# M90E36A.net
KiCad netlist of a schematic drawn in EAGLE
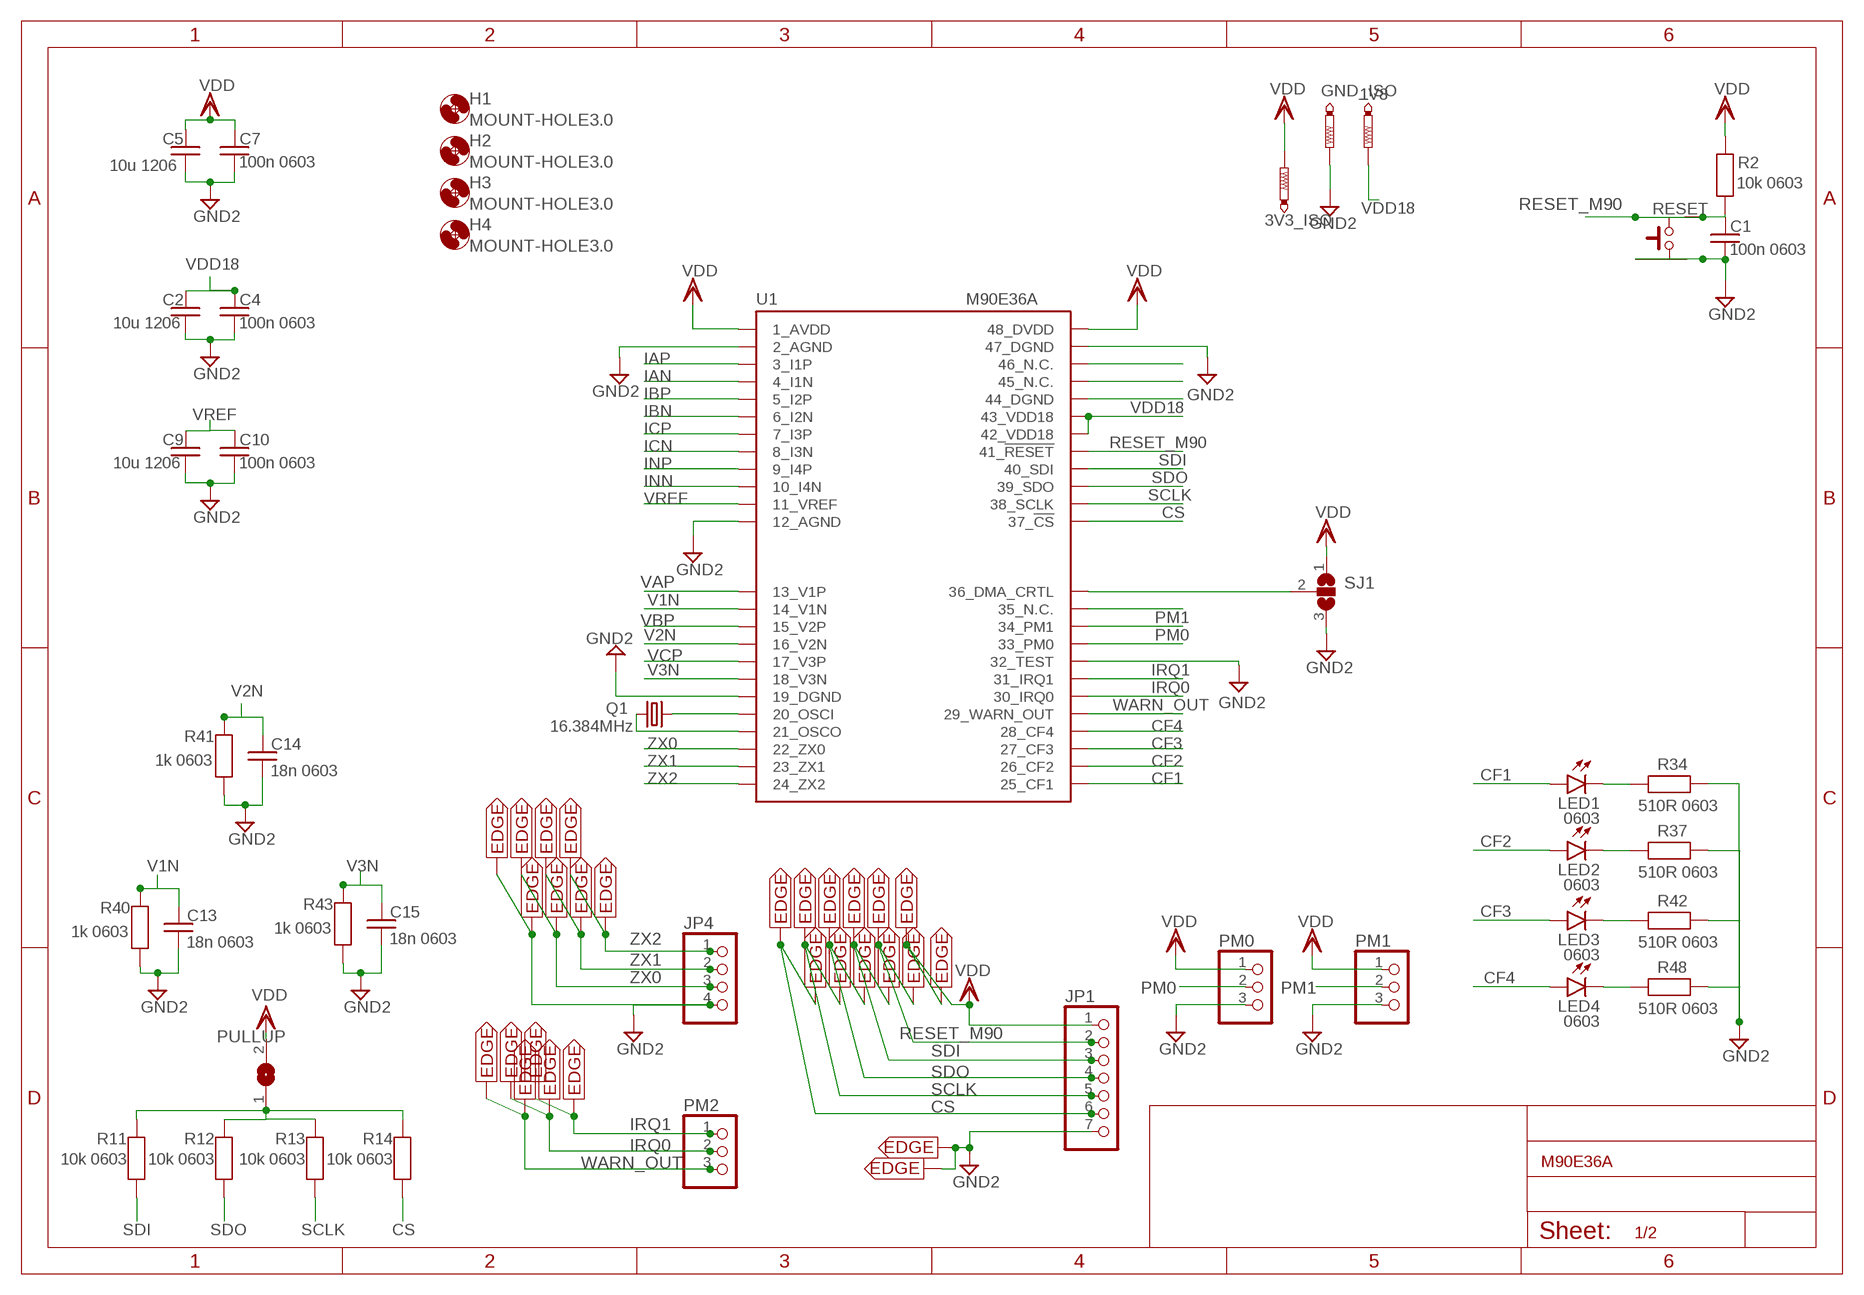
[diagram p0: schematic, sheet 1]
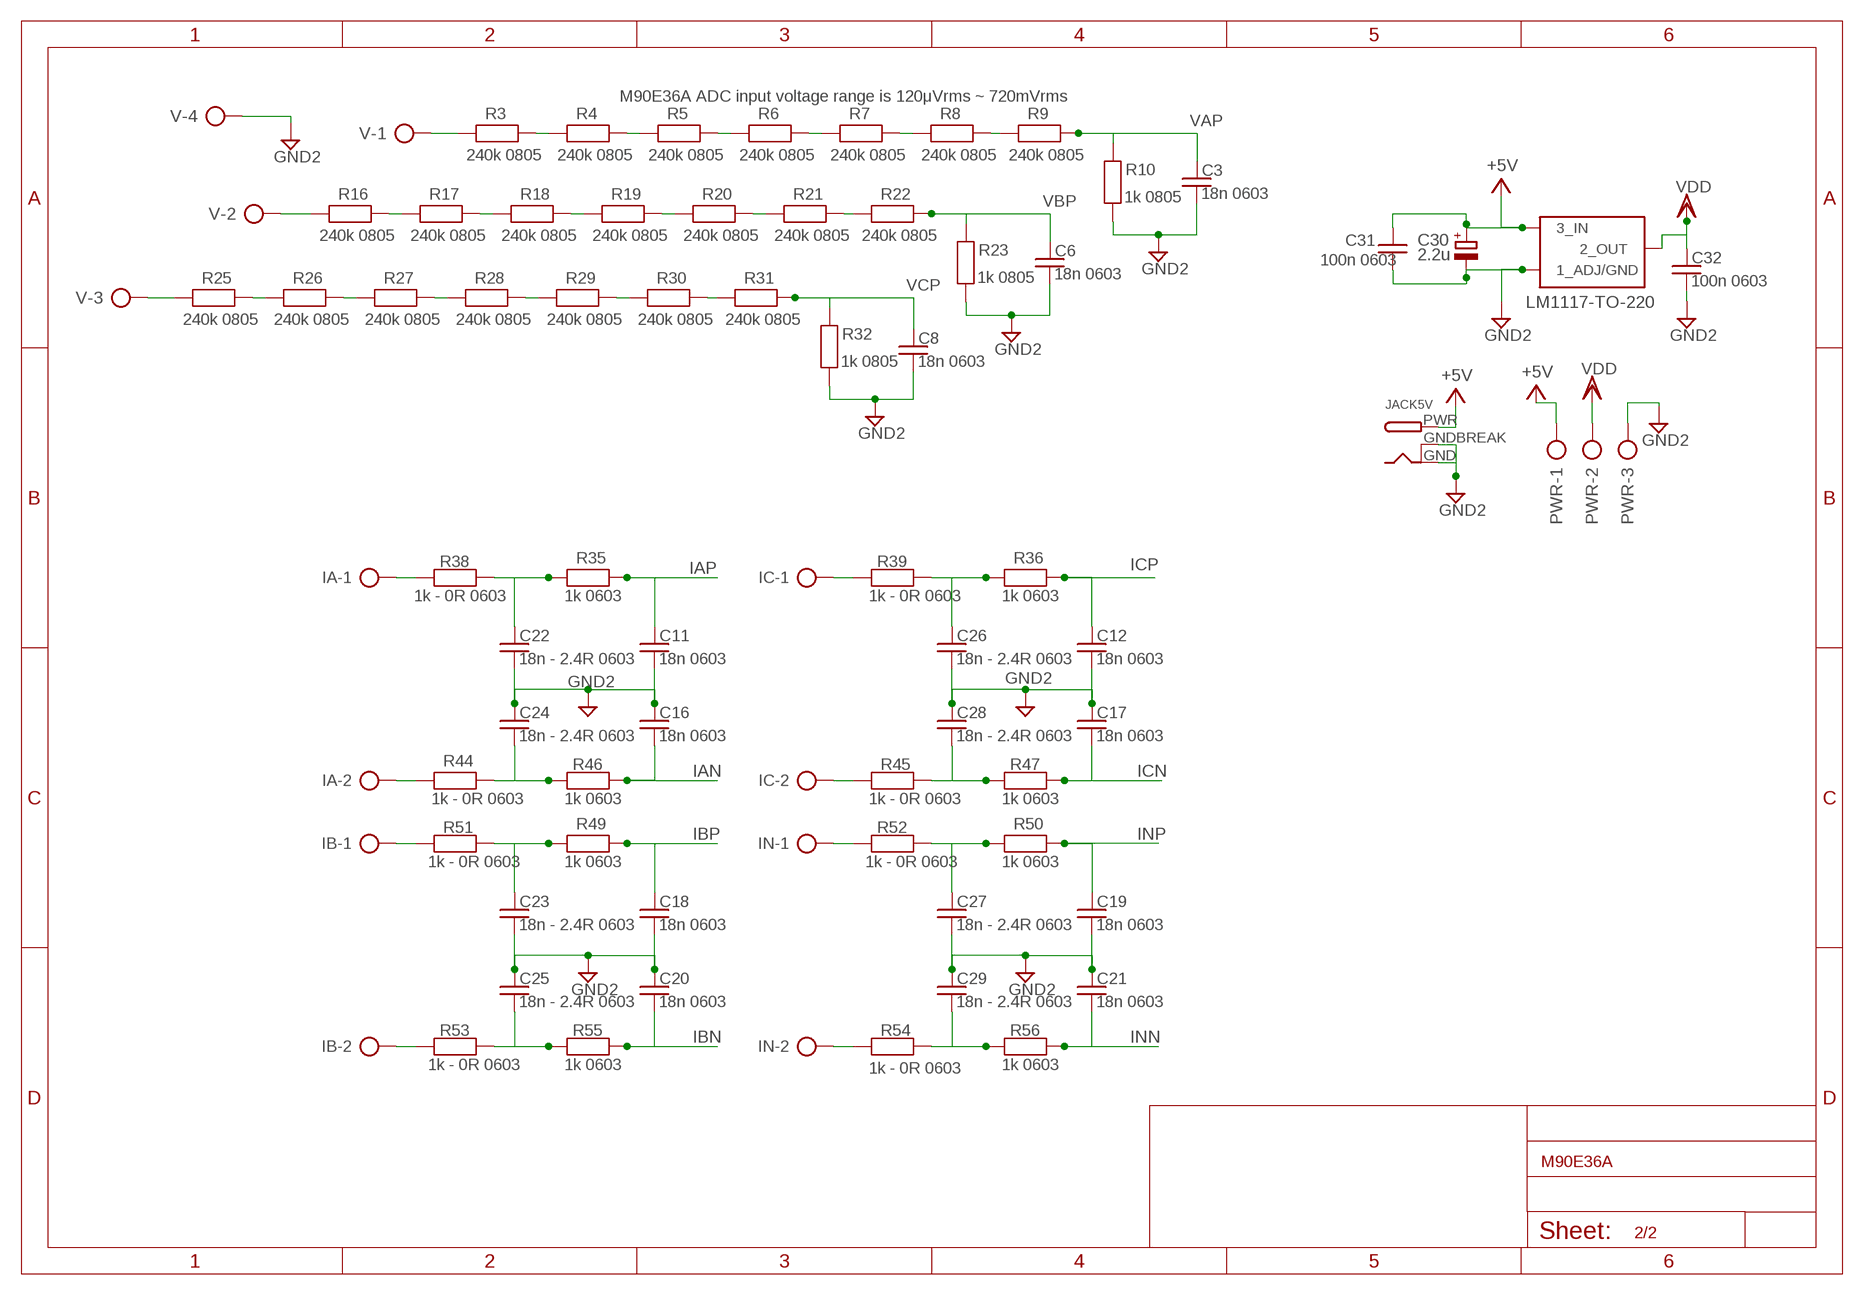
[diagram p1: schematic, sheet 2]

(export (version "E")
  (design (tool "Eeschema 10.0.6"))
  (components
    (comp (ref "C3")
      (value "18n 0603")
      (footprint "eagle-import:0603_IMPERIAL")
      (libsource (lib "eagle-import") (part "C0603"))
    )
    (comp (ref "C6")
      (value "18n 0603")
      (footprint "eagle-import:0603_IMPERIAL")
      (libsource (lib "eagle-import") (part "C0603"))
    )
    (comp (ref "C8")
      (value "18n 0603")
      (footprint "eagle-import:0603_IMPERIAL")
      (libsource (lib "eagle-import") (part "C0603"))
    )
    (comp (ref "C11")
      (value "18n 0603")
      (footprint "eagle-import:0603_IMPERIAL")
      (libsource (lib "eagle-import") (part "C0603"))
    )
    (comp (ref "C12")
      (value "18n 0603")
      (footprint "eagle-import:0603_IMPERIAL")
      (libsource (lib "eagle-import") (part "C0603"))
    )
    (comp (ref "C16")
      (value "18n 0603")
      (footprint "eagle-import:0603_IMPERIAL")
      (libsource (lib "eagle-import") (part "C0603"))
    )
    (comp (ref "C17")
      (value "18n 0603")
      (footprint "eagle-import:0603_IMPERIAL")
      (libsource (lib "eagle-import") (part "C0603"))
    )
    (comp (ref "C18")
      (value "18n 0603")
      (footprint "eagle-import:0603_IMPERIAL")
      (libsource (lib "eagle-import") (part "C0603"))
    )
    (comp (ref "C19")
      (value "18n 0603")
      (footprint "eagle-import:0603_IMPERIAL")
      (libsource (lib "eagle-import") (part "C0603"))
    )
    (comp (ref "C20")
      (value "18n 0603")
      (footprint "eagle-import:0603_IMPERIAL")
      (libsource (lib "eagle-import") (part "C0603"))
    )
    (comp (ref "C21")
      (value "18n 0603")
      (footprint "eagle-import:0603_IMPERIAL")
      (libsource (lib "eagle-import") (part "C0603"))
    )
    (comp (ref "C22")
      (value "18n - 2.4R 0603")
      (footprint "eagle-import:0603_IMPERIAL")
      (libsource (lib "eagle-import") (part "C0603"))
    )
    (comp (ref "C23")
      (value "18n - 2.4R 0603")
      (footprint "eagle-import:0603_IMPERIAL")
      (libsource (lib "eagle-import") (part "C0603"))
    )
    (comp (ref "C24")
      (value "18n - 2.4R 0603")
      (footprint "eagle-import:0603_IMPERIAL")
      (libsource (lib "eagle-import") (part "C0603"))
    )
    (comp (ref "C25")
      (value "18n - 2.4R 0603")
      (footprint "eagle-import:0603_IMPERIAL")
      (libsource (lib "eagle-import") (part "C0603"))
    )
    (comp (ref "C26")
      (value "18n - 2.4R 0603")
      (footprint "eagle-import:0603_IMPERIAL")
      (libsource (lib "eagle-import") (part "C0603"))
    )
    (comp (ref "C27")
      (value "18n - 2.4R 0603")
      (footprint "eagle-import:0603_IMPERIAL")
      (libsource (lib "eagle-import") (part "C0603"))
    )
    (comp (ref "C28")
      (value "18n - 2.4R 0603")
      (footprint "eagle-import:0603_IMPERIAL")
      (libsource (lib "eagle-import") (part "C0603"))
    )
    (comp (ref "C29")
      (value "18n - 2.4R 0603")
      (footprint "eagle-import:0603_IMPERIAL")
      (libsource (lib "eagle-import") (part "C0603"))
    )
    (comp (ref "C30")
      (value "2.2u")
      (footprint "eagle-import:E2,5-5")
      (libsource (lib "eagle-import") (part "CPOL-EUE2.5-5"))
    )
    (comp (ref "C31")
      (value "100n 0603")
      (footprint "eagle-import:0603_IMPERIAL")
      (libsource (lib "eagle-import") (part "C0603"))
    )
    (comp (ref "C32")
      (value "100n 0603")
      (footprint "eagle-import:0603_IMPERIAL")
      (libsource (lib "eagle-import") (part "C0603"))
    )
    (comp (ref "IA")
      (value "AK500/2")
      (footprint "eagle-import:AK500_2")
      (libsource (lib "eagle-import") (part "AK500/2"))
    )
    (comp (ref "IB")
      (value "AK500/2")
      (footprint "eagle-import:AK500_2")
      (libsource (lib "eagle-import") (part "AK500/2"))
    )
    (comp (ref "IC")
      (value "AK500/2")
      (footprint "eagle-import:AK500_2")
      (libsource (lib "eagle-import") (part "AK500/2"))
    )
    (comp (ref "IN")
      (value "AK500/2")
      (footprint "eagle-import:AK500_2")
      (libsource (lib "eagle-import") (part "AK500/2"))
    )
    (comp (ref "JACK5V")
      (value "DCBARRELPTH")
      (footprint "eagle-import:DCJACK_2MM_PTH")
      (libsource (lib "eagle-import") (part "DCBARRELPTH"))
    )
    (comp (ref "PWR")
      (value "AK500/3")
      (footprint "eagle-import:AK500_3")
      (libsource (lib "eagle-import") (part "AK500/3"))
    )
    (comp (ref "R3")
      (value "240k 0805")
      (footprint "eagle-import:0805_IMPERIAL")
      (libsource (lib "eagle-import") (part "R0805"))
    )
    (comp (ref "R4")
      (value "240k 0805")
      (footprint "eagle-import:0805_IMPERIAL")
      (libsource (lib "eagle-import") (part "R0805"))
    )
    (comp (ref "R5")
      (value "240k 0805")
      (footprint "eagle-import:0805_IMPERIAL")
      (libsource (lib "eagle-import") (part "R0805"))
    )
    (comp (ref "R6")
      (value "240k 0805")
      (footprint "eagle-import:0805_IMPERIAL")
      (libsource (lib "eagle-import") (part "R0805"))
    )
    (comp (ref "R7")
      (value "240k 0805")
      (footprint "eagle-import:0805_IMPERIAL")
      (libsource (lib "eagle-import") (part "R0805"))
    )
    (comp (ref "R8")
      (value "240k 0805")
      (footprint "eagle-import:0805_IMPERIAL")
      (libsource (lib "eagle-import") (part "R0805"))
    )
    (comp (ref "R9")
      (value "240k 0805")
      (footprint "eagle-import:0805_IMPERIAL")
      (libsource (lib "eagle-import") (part "R0805"))
    )
    (comp (ref "R10")
      (value "1k 0805")
      (footprint "eagle-import:0805_IMPERIAL")
      (libsource (lib "eagle-import") (part "R0805"))
    )
    (comp (ref "R16")
      (value "240k 0805")
      (footprint "eagle-import:0805_IMPERIAL")
      (libsource (lib "eagle-import") (part "R0805"))
    )
    (comp (ref "R17")
      (value "240k 0805")
      (footprint "eagle-import:0805_IMPERIAL")
      (libsource (lib "eagle-import") (part "R0805"))
    )
    (comp (ref "R18")
      (value "240k 0805")
      (footprint "eagle-import:0805_IMPERIAL")
      (libsource (lib "eagle-import") (part "R0805"))
    )
    (comp (ref "R19")
      (value "240k 0805")
      (footprint "eagle-import:0805_IMPERIAL")
      (libsource (lib "eagle-import") (part "R0805"))
    )
    (comp (ref "R20")
      (value "240k 0805")
      (footprint "eagle-import:0805_IMPERIAL")
      (libsource (lib "eagle-import") (part "R0805"))
    )
    (comp (ref "R21")
      (value "240k 0805")
      (footprint "eagle-import:0805_IMPERIAL")
      (libsource (lib "eagle-import") (part "R0805"))
    )
    (comp (ref "R22")
      (value "240k 0805")
      (footprint "eagle-import:0805_IMPERIAL")
      (libsource (lib "eagle-import") (part "R0805"))
    )
    (comp (ref "R23")
      (value "1k 0805")
      (footprint "eagle-import:0805_IMPERIAL")
      (libsource (lib "eagle-import") (part "R0805"))
    )
    (comp (ref "R25")
      (value "240k 0805")
      (footprint "eagle-import:0805_IMPERIAL")
      (libsource (lib "eagle-import") (part "R0805"))
    )
    (comp (ref "R26")
      (value "240k 0805")
      (footprint "eagle-import:0805_IMPERIAL")
      (libsource (lib "eagle-import") (part "R0805"))
    )
    (comp (ref "R27")
      (value "240k 0805")
      (footprint "eagle-import:0805_IMPERIAL")
      (libsource (lib "eagle-import") (part "R0805"))
    )
    (comp (ref "R28")
      (value "240k 0805")
      (footprint "eagle-import:0805_IMPERIAL")
      (libsource (lib "eagle-import") (part "R0805"))
    )
    (comp (ref "R29")
      (value "240k 0805")
      (footprint "eagle-import:0805_IMPERIAL")
      (libsource (lib "eagle-import") (part "R0805"))
    )
    (comp (ref "R30")
      (value "240k 0805")
      (footprint "eagle-import:0805_IMPERIAL")
      (libsource (lib "eagle-import") (part "R0805"))
    )
    (comp (ref "R31")
      (value "240k 0805")
      (footprint "eagle-import:0805_IMPERIAL")
      (libsource (lib "eagle-import") (part "R0805"))
    )
    (comp (ref "R32")
      (value "1k 0805")
      (footprint "eagle-import:0805_IMPERIAL")
      (libsource (lib "eagle-import") (part "R0805"))
    )
    (comp (ref "R35")
      (value "1k 0603")
      (footprint "eagle-import:0603_IMPERIAL")
      (libsource (lib "eagle-import") (part "R0603"))
    )
    (comp (ref "R36")
      (value "1k 0603")
      (footprint "eagle-import:0603_IMPERIAL")
      (libsource (lib "eagle-import") (part "R0603"))
    )
    (comp (ref "R38")
      (value "1k - 0R 0603")
      (footprint "eagle-import:0603_IMPERIAL")
      (libsource (lib "eagle-import") (part "R0603"))
    )
    (comp (ref "R39")
      (value "1k - 0R 0603")
      (footprint "eagle-import:0603_IMPERIAL")
      (libsource (lib "eagle-import") (part "R0603"))
    )
    (comp (ref "R44")
      (value "1k - 0R 0603")
      (footprint "eagle-import:0603_IMPERIAL")
      (libsource (lib "eagle-import") (part "R0603"))
    )
    (comp (ref "R45")
      (value "1k - 0R 0603")
      (footprint "eagle-import:0603_IMPERIAL")
      (libsource (lib "eagle-import") (part "R0603"))
    )
    (comp (ref "R46")
      (value "1k 0603")
      (footprint "eagle-import:0603_IMPERIAL")
      (libsource (lib "eagle-import") (part "R0603"))
    )
    (comp (ref "R47")
      (value "1k 0603")
      (footprint "eagle-import:0603_IMPERIAL")
      (libsource (lib "eagle-import") (part "R0603"))
    )
    (comp (ref "R49")
      (value "1k 0603")
      (footprint "eagle-import:0603_IMPERIAL")
      (libsource (lib "eagle-import") (part "R0603"))
    )
    (comp (ref "R50")
      (value "1k 0603")
      (footprint "eagle-import:0603_IMPERIAL")
      (libsource (lib "eagle-import") (part "R0603"))
    )
    (comp (ref "R51")
      (value "1k - 0R 0603")
      (footprint "eagle-import:0603_IMPERIAL")
      (libsource (lib "eagle-import") (part "R0603"))
    )
    (comp (ref "R52")
      (value "1k - 0R 0603")
      (footprint "eagle-import:0603_IMPERIAL")
      (libsource (lib "eagle-import") (part "R0603"))
    )
    (comp (ref "R53")
      (value "1k - 0R 0603")
      (footprint "eagle-import:0603_IMPERIAL")
      (libsource (lib "eagle-import") (part "R0603"))
    )
    (comp (ref "R54")
      (value "1k - 0R 0603")
      (footprint "eagle-import:0603_IMPERIAL")
      (libsource (lib "eagle-import") (part "R0603"))
    )
    (comp (ref "R55")
      (value "1k 0603")
      (footprint "eagle-import:0603_IMPERIAL")
      (libsource (lib "eagle-import") (part "R0603"))
    )
    (comp (ref "R56")
      (value "1k 0603")
      (footprint "eagle-import:0603_IMPERIAL")
      (libsource (lib "eagle-import") (part "R0603"))
    )
    (comp (ref "U3")
      (value "LM1117-TO-220")
      (footprint "eagle-import:TO-220")
      (libsource (lib "eagle-import") (part "LM1117-TO-220"))
    )
    (comp (ref "V")
      (value "AK500/4")
      (footprint "eagle-import:AK500_4")
      (libsource (lib "eagle-import") (part "AK500/4"))
    )
    (comp (ref "1V8")
      (value "PTR1TP19R")
      (footprint "eagle-import:TP19R")
      (libsource (lib "eagle-import") (part "PTR1TP19R"))
    )
    (comp (ref "3V3_ISO")
      (value "PTR1TP19R")
      (footprint "eagle-import:TP19R")
      (libsource (lib "eagle-import") (part "PTR1TP19R"))
    )
    (comp (ref "C1")
      (value "100n 0603")
      (footprint "eagle-import:0603_IMPERIAL")
      (libsource (lib "eagle-import") (part "C0603"))
    )
    (comp (ref "C2")
      (value "10u 1206")
      (footprint "eagle-import:1206_IMPERIAL")
      (libsource (lib "eagle-import") (part "C1206"))
    )
    (comp (ref "C4")
      (value "100n 0603")
      (footprint "eagle-import:0603_IMPERIAL")
      (libsource (lib "eagle-import") (part "C0603"))
    )
    (comp (ref "C5")
      (value "10u 1206")
      (footprint "eagle-import:1206_IMPERIAL")
      (libsource (lib "eagle-import") (part "C1206"))
    )
    (comp (ref "C7")
      (value "100n 0603")
      (footprint "eagle-import:0603_IMPERIAL")
      (libsource (lib "eagle-import") (part "C0603"))
    )
    (comp (ref "C9")
      (value "10u 1206")
      (footprint "eagle-import:1206_IMPERIAL")
      (libsource (lib "eagle-import") (part "C1206"))
    )
    (comp (ref "C10")
      (value "100n 0603")
      (footprint "eagle-import:0603_IMPERIAL")
      (libsource (lib "eagle-import") (part "C0603"))
    )
    (comp (ref "C13")
      (value "18n 0603")
      (footprint "eagle-import:0603_IMPERIAL")
      (libsource (lib "eagle-import") (part "C0603"))
    )
    (comp (ref "C14")
      (value "18n 0603")
      (footprint "eagle-import:0603_IMPERIAL")
      (libsource (lib "eagle-import") (part "C0603"))
    )
    (comp (ref "C15")
      (value "18n 0603")
      (footprint "eagle-import:0603_IMPERIAL")
      (libsource (lib "eagle-import") (part "C0603"))
    )
    (comp (ref "GND_ISO")
      (value "PTR1TP19R")
      (footprint "eagle-import:TP19R")
      (libsource (lib "eagle-import") (part "PTR1TP19R"))
    )
    (comp (ref "H1")
      (value "MOUNT-HOLE3.0")
      (footprint "eagle-import:3,0")
      (libsource (lib "eagle-import") (part "MOUNT-HOLE3.0"))
    )
    (comp (ref "H2")
      (value "MOUNT-HOLE3.0")
      (footprint "eagle-import:3,0")
      (libsource (lib "eagle-import") (part "MOUNT-HOLE3.0"))
    )
    (comp (ref "H3")
      (value "MOUNT-HOLE3.0")
      (footprint "eagle-import:3,0")
      (libsource (lib "eagle-import") (part "MOUNT-HOLE3.0"))
    )
    (comp (ref "H4")
      (value "MOUNT-HOLE3.0")
      (footprint "eagle-import:3,0")
      (libsource (lib "eagle-import") (part "MOUNT-HOLE3.0"))
    )
    (comp (ref "JP1")
      (value "PINHD-1X7")
      (footprint "eagle-import:1X07")
      (libsource (lib "eagle-import") (part "PINHD-1X7"))
    )
    (comp (ref "JP4")
      (value "PINHD-1X4")
      (footprint "eagle-import:1X04")
      (libsource (lib "eagle-import") (part "PINHD-1X4"))
    )
    (comp (ref "LED1")
      (value "0603")
      (footprint "eagle-import:CHIPLED_0805")
      (libsource (lib "eagle-import") (part "LEDCHIPLED_0805"))
    )
    (comp (ref "LED2")
      (value "0603")
      (footprint "eagle-import:CHIPLED_0805")
      (libsource (lib "eagle-import") (part "LEDCHIPLED_0805"))
    )
    (comp (ref "LED3")
      (value "0603")
      (footprint "eagle-import:CHIPLED_0805")
      (libsource (lib "eagle-import") (part "LEDCHIPLED_0805"))
    )
    (comp (ref "LED4")
      (value "0603")
      (footprint "eagle-import:CHIPLED_0805")
      (libsource (lib "eagle-import") (part "LEDCHIPLED_0805"))
    )
    (comp (ref "PM0")
      (value "PINHD-1X3")
      (footprint "eagle-import:1X03")
      (libsource (lib "eagle-import") (part "PINHD-1X3"))
    )
    (comp (ref "PM1")
      (value "PINHD-1X3")
      (footprint "eagle-import:1X03")
      (libsource (lib "eagle-import") (part "PINHD-1X3"))
    )
    (comp (ref "PM2")
      (value "PINHD-1X3")
      (footprint "eagle-import:1X03")
      (libsource (lib "eagle-import") (part "PINHD-1X3"))
    )
    (comp (ref "PULLUP")
      (value "SJ")
      (footprint "eagle-import:SJ")
      (libsource (lib "eagle-import") (part "SJ"))
    )
    (comp (ref "Q1")
      (value "16.384MHz")
      (footprint "eagle-import:HC49UP")
      (libsource (lib "eagle-import") (part "CRYSTALHC49UP"))
    )
    (comp (ref "R2")
      (value "10k 0603")
      (footprint "eagle-import:0603_IMPERIAL")
      (libsource (lib "eagle-import") (part "R0603"))
    )
    (comp (ref "R11")
      (value "10k 0603")
      (footprint "eagle-import:0603_IMPERIAL")
      (libsource (lib "eagle-import") (part "R0603"))
    )
    (comp (ref "R12")
      (value "10k 0603")
      (footprint "eagle-import:0603_IMPERIAL")
      (libsource (lib "eagle-import") (part "R0603"))
    )
    (comp (ref "R13")
      (value "10k 0603")
      (footprint "eagle-import:0603_IMPERIAL")
      (libsource (lib "eagle-import") (part "R0603"))
    )
    (comp (ref "R14")
      (value "10k 0603")
      (footprint "eagle-import:0603_IMPERIAL")
      (libsource (lib "eagle-import") (part "R0603"))
    )
    (comp (ref "R34")
      (value "510R 0603")
      (footprint "eagle-import:0603_IMPERIAL")
      (libsource (lib "eagle-import") (part "R0603"))
    )
    (comp (ref "R37")
      (value "510R 0603")
      (footprint "eagle-import:0603_IMPERIAL")
      (libsource (lib "eagle-import") (part "R0603"))
    )
    (comp (ref "R40")
      (value "1k 0603")
      (footprint "eagle-import:0603_IMPERIAL")
      (libsource (lib "eagle-import") (part "R0603"))
    )
    (comp (ref "R41")
      (value "1k 0603")
      (footprint "eagle-import:0603_IMPERIAL")
      (libsource (lib "eagle-import") (part "R0603"))
    )
    (comp (ref "R42")
      (value "510R 0603")
      (footprint "eagle-import:0603_IMPERIAL")
      (libsource (lib "eagle-import") (part "R0603"))
    )
    (comp (ref "R43")
      (value "1k 0603")
      (footprint "eagle-import:0603_IMPERIAL")
      (libsource (lib "eagle-import") (part "R0603"))
    )
    (comp (ref "R48")
      (value "510R 0603")
      (footprint "eagle-import:0603_IMPERIAL")
      (libsource (lib "eagle-import") (part "R0603"))
    )
    (comp (ref "RESET")
      (value "TACTILE_SWITCHPTH")
      (footprint "eagle-import:TACTILE_SWITCH_PTH")
      (fields (field (name "PARTNUMBER") "A06"))
      (libsource (lib "eagle-import") (part "TACTILE_SWITCHPTH"))
    )
    (comp (ref "SJ1")
      (value "SJ2W")
      (footprint "eagle-import:SJ_2")
      (libsource (lib "eagle-import") (part "SJ2W"))
    )
    (comp (ref "U$1")
      (value "EDGE")
      (footprint "eagle-import:EDGE")
      (libsource (lib "eagle-import") (part "EDGE"))
    )
    (comp (ref "U$2")
      (value "EDGE")
      (footprint "eagle-import:EDGE")
      (libsource (lib "eagle-import") (part "EDGE"))
    )
    (comp (ref "U$3")
      (value "EDGE")
      (footprint "eagle-import:EDGE")
      (libsource (lib "eagle-import") (part "EDGE"))
    )
    (comp (ref "U$4")
      (value "EDGE")
      (footprint "eagle-import:EDGE")
      (libsource (lib "eagle-import") (part "EDGE"))
    )
    (comp (ref "U$5")
      (value "EDGE")
      (footprint "eagle-import:EDGE")
      (libsource (lib "eagle-import") (part "EDGE"))
    )
    (comp (ref "U$6")
      (value "EDGE")
      (footprint "eagle-import:EDGE")
      (libsource (lib "eagle-import") (part "EDGE"))
    )
    (comp (ref "U$7")
      (value "EDGE")
      (footprint "eagle-import:EDGE")
      (libsource (lib "eagle-import") (part "EDGE"))
    )
    (comp (ref "U$8")
      (value "EDGE")
      (footprint "eagle-import:EDGE")
      (libsource (lib "eagle-import") (part "EDGE"))
    )
    (comp (ref "U$9")
      (value "EDGE")
      (footprint "eagle-import:EDGE")
      (libsource (lib "eagle-import") (part "EDGE"))
    )
    (comp (ref "U$10")
      (value "EDGE")
      (footprint "eagle-import:EDGE")
      (libsource (lib "eagle-import") (part "EDGE"))
    )
    (comp (ref "U$11")
      (value "EDGE")
      (footprint "eagle-import:EDGE")
      (libsource (lib "eagle-import") (part "EDGE"))
    )
    (comp (ref "U$12")
      (value "EDGE")
      (footprint "eagle-import:EDGE")
      (libsource (lib "eagle-import") (part "EDGE"))
    )
    (comp (ref "U$13")
      (value "EDGE")
      (footprint "eagle-import:EDGE")
      (libsource (lib "eagle-import") (part "EDGE"))
    )
    (comp (ref "U$14")
      (value "EDGE")
      (footprint "eagle-import:EDGE")
      (libsource (lib "eagle-import") (part "EDGE"))
    )
    (comp (ref "U$15")
      (value "EDGE")
      (footprint "eagle-import:EDGE")
      (libsource (lib "eagle-import") (part "EDGE"))
    )
    (comp (ref "U$16")
      (value "EDGE")
      (footprint "eagle-import:EDGE")
      (libsource (lib "eagle-import") (part "EDGE"))
    )
    (comp (ref "U$17")
      (value "EDGE")
      (footprint "eagle-import:EDGE")
      (libsource (lib "eagle-import") (part "EDGE"))
    )
    (comp (ref "U$18")
      (value "EDGE")
      (footprint "eagle-import:EDGE")
      (libsource (lib "eagle-import") (part "EDGE"))
    )
    (comp (ref "U$19")
      (value "EDGE")
      (footprint "eagle-import:EDGE")
      (libsource (lib "eagle-import") (part "EDGE"))
    )
    (comp (ref "U$20")
      (value "EDGE")
      (footprint "eagle-import:EDGE")
      (libsource (lib "eagle-import") (part "EDGE"))
    )
    (comp (ref "U$21")
      (value "EDGE")
      (footprint "eagle-import:EDGE")
      (libsource (lib "eagle-import") (part "EDGE"))
    )
    (comp (ref "U$22")
      (value "EDGE")
      (footprint "eagle-import:EDGE")
      (libsource (lib "eagle-import") (part "EDGE"))
    )
    (comp (ref "U$23")
      (value "EDGE")
      (footprint "eagle-import:EDGE")
      (libsource (lib "eagle-import") (part "EDGE"))
    )
    (comp (ref "U$24")
      (value "EDGE")
      (footprint "eagle-import:EDGE")
      (libsource (lib "eagle-import") (part "EDGE"))
    )
    (comp (ref "U$25")
      (value "EDGE")
      (footprint "eagle-import:EDGE")
      (libsource (lib "eagle-import") (part "EDGE"))
    )
    (comp (ref "U$26")
      (value "EDGE")
      (footprint "eagle-import:EDGE")
      (libsource (lib "eagle-import") (part "EDGE"))
    )
    (comp (ref "U$27")
      (value "EDGE")
      (footprint "eagle-import:EDGE")
      (libsource (lib "eagle-import") (part "EDGE"))
    )
    (comp (ref "U$28")
      (value "EDGE")
      (footprint "eagle-import:EDGE")
      (libsource (lib "eagle-import") (part "EDGE"))
    )
    (comp (ref "U1")
      (value "M90E36A")
      (footprint "eagle-import:TQFP-48")
      (fields (field (name "PARTNUMBER") "ATM90E36A-AU-Y"))
      (libsource (lib "eagle-import") (part "M90E36A"))
    )
  )
  (nets
    (net (code "1") (name "+5V") (class "Default")
      (node (ref "C30") (pin "+") (pinfunction "+_+") (pintype "passive"))
      (node (ref "C31") (pin "P$2") (pinfunction "P$2_P$2") (pintype "bidirectional"))
      (node (ref "JACK5V") (pin "PWR") (pinfunction "PWR_PWR") (pintype "power_in"))
      (node (ref "PWR") (pin "1") (pinfunction "KL_1") (pintype "passive"))
      (node (ref "U3") (pin "3") (pinfunction "3_IN_3") (pintype "input"))
    )
    (net (code "2") (name "CF1") (class "Default")
      (node (ref "LED1") (pin "A") (pinfunction "A_A") (pintype "passive"))
      (node (ref "U1") (pin "P$25") (pinfunction "25_CF1_P$25") (pintype "bidirectional"))
    )
    (net (code "3") (name "CF2") (class "Default")
      (node (ref "LED2") (pin "A") (pinfunction "A_A") (pintype "passive"))
      (node (ref "U1") (pin "P$26") (pinfunction "26_CF2_P$26") (pintype "bidirectional"))
    )
    (net (code "4") (name "CF3") (class "Default")
      (node (ref "LED3") (pin "A") (pinfunction "A_A") (pintype "passive"))
      (node (ref "U1") (pin "P$27") (pinfunction "27_CF3_P$27") (pintype "bidirectional"))
    )
    (net (code "5") (name "CF4") (class "Default")
      (node (ref "LED4") (pin "A") (pinfunction "A_A") (pintype "passive"))
      (node (ref "U1") (pin "P$28") (pinfunction "28_CF4_P$28") (pintype "bidirectional"))
    )
    (net (code "6") (name "CS") (class "Default")
      (node (ref "JP1") (pin "6") (pinfunction "6_6") (pintype "passive"))
      (node (ref "R14") (pin "P$1") (pinfunction "P$1_P$1") (pintype "bidirectional"))
      (node (ref "U$25") (pin "P$1") (pinfunction "P$1_P$1") (pintype "bidirectional"))
      (node (ref "U$4") (pin "P$1") (pinfunction "P$1_P$1") (pintype "bidirectional"))
      (node (ref "U1") (pin "P$37") (pinfunction "37_~{CS}_P$37") (pintype "bidirectional"))
    )
    (net (code "7") (name "GND2") (class "Default")
      (node (ref "C1") (pin "P$1") (pinfunction "P$1_P$1") (pintype "bidirectional"))
      (node (ref "C10") (pin "P$1") (pinfunction "P$1_P$1") (pintype "bidirectional"))
      (node (ref "C11") (pin "P$1") (pinfunction "P$1_P$1") (pintype "bidirectional"))
      (node (ref "C12") (pin "P$1") (pinfunction "P$1_P$1") (pintype "bidirectional"))
      (node (ref "C13") (pin "P$1") (pinfunction "P$1_P$1") (pintype "bidirectional"))
      (node (ref "C14") (pin "P$1") (pinfunction "P$1_P$1") (pintype "bidirectional"))
      (node (ref "C15") (pin "P$1") (pinfunction "P$1_P$1") (pintype "bidirectional"))
      (node (ref "C16") (pin "P$2") (pinfunction "P$2_P$2") (pintype "bidirectional"))
      (node (ref "C17") (pin "P$2") (pinfunction "P$2_P$2") (pintype "bidirectional"))
      (node (ref "C18") (pin "P$1") (pinfunction "P$1_P$1") (pintype "bidirectional"))
      (node (ref "C19") (pin "P$1") (pinfunction "P$1_P$1") (pintype "bidirectional"))
      (node (ref "C2") (pin "P$1") (pinfunction "P$1_P$1") (pintype "bidirectional"))
      (node (ref "C20") (pin "P$2") (pinfunction "P$2_P$2") (pintype "bidirectional"))
      (node (ref "C21") (pin "P$2") (pinfunction "P$2_P$2") (pintype "bidirectional"))
      (node (ref "C22") (pin "P$1") (pinfunction "P$1_P$1") (pintype "bidirectional"))
      (node (ref "C23") (pin "P$1") (pinfunction "P$1_P$1") (pintype "bidirectional"))
      (node (ref "C24") (pin "P$2") (pinfunction "P$2_P$2") (pintype "bidirectional"))
      (node (ref "C25") (pin "P$2") (pinfunction "P$2_P$2") (pintype "bidirectional"))
      (node (ref "C26") (pin "P$1") (pinfunction "P$1_P$1") (pintype "bidirectional"))
      (node (ref "C27") (pin "P$1") (pinfunction "P$1_P$1") (pintype "bidirectional"))
      (node (ref "C28") (pin "P$2") (pinfunction "P$2_P$2") (pintype "bidirectional"))
      (node (ref "C29") (pin "P$2") (pinfunction "P$2_P$2") (pintype "bidirectional"))
      (node (ref "C3") (pin "P$1") (pinfunction "P$1_P$1") (pintype "bidirectional"))
      (node (ref "C30") (pin "-") (pinfunction "-_-") (pintype "passive"))
      (node (ref "C31") (pin "P$1") (pinfunction "P$1_P$1") (pintype "bidirectional"))
      (node (ref "C32") (pin "P$1") (pinfunction "P$1_P$1") (pintype "bidirectional"))
      (node (ref "C4") (pin "P$1") (pinfunction "P$1_P$1") (pintype "bidirectional"))
      (node (ref "C5") (pin "P$1") (pinfunction "P$1_P$1") (pintype "bidirectional"))
      (node (ref "C6") (pin "P$1") (pinfunction "P$1_P$1") (pintype "bidirectional"))
      (node (ref "C7") (pin "P$1") (pinfunction "P$1_P$1") (pintype "bidirectional"))
      (node (ref "C8") (pin "P$1") (pinfunction "P$1_P$1") (pintype "bidirectional"))
      (node (ref "C9") (pin "P$1") (pinfunction "P$1_P$1") (pintype "bidirectional"))
      (node (ref "GND_ISO") (pin "TP") (pinfunction "TP_TP") (pintype "input"))
      (node (ref "JACK5V") (pin "GND") (pinfunction "GND_GND") (pintype "power_in"))
      (node (ref "JACK5V") (pin "GNDBREAK") (pinfunction "GNDBREAK_GNDBREAK") (pintype "power_in"))
      (node (ref "JP1") (pin "7") (pinfunction "7_7") (pintype "passive"))
      (node (ref "JP4") (pin "4") (pinfunction "4_4") (pintype "passive"))
      (node (ref "PM0") (pin "3") (pinfunction "3_3") (pintype "passive"))
      (node (ref "PM1") (pin "3") (pinfunction "3_3") (pintype "passive"))
      (node (ref "PWR") (pin "3") (pinfunction "KL_3") (pintype "passive"))
      (node (ref "R10") (pin "P$1") (pinfunction "P$1_P$1") (pintype "bidirectional"))
      (node (ref "R23") (pin "P$1") (pinfunction "P$1_P$1") (pintype "bidirectional"))
      (node (ref "R32") (pin "P$1") (pinfunction "P$1_P$1") (pintype "bidirectional"))
      (node (ref "R34") (pin "P$2") (pinfunction "P$2_P$2") (pintype "bidirectional"))
      (node (ref "R37") (pin "P$2") (pinfunction "P$2_P$2") (pintype "bidirectional"))
      (node (ref "R40") (pin "P$1") (pinfunction "P$1_P$1") (pintype "bidirectional"))
      (node (ref "R41") (pin "P$1") (pinfunction "P$1_P$1") (pintype "bidirectional"))
      (node (ref "R42") (pin "P$2") (pinfunction "P$2_P$2") (pintype "bidirectional"))
      (node (ref "R43") (pin "P$1") (pinfunction "P$1_P$1") (pintype "bidirectional"))
      (node (ref "R48") (pin "P$2") (pinfunction "P$2_P$2") (pintype "bidirectional"))
      (node (ref "RESET") (pin "P$1") (pinfunction "1_P$1") (pintype "bidirectional"))
      (node (ref "RESET") (pin "P$2") (pinfunction "2_P$2") (pintype "bidirectional"))
      (node (ref "SJ1") (pin "3") (pinfunction "3_3") (pintype "passive"))
      (node (ref "U$10") (pin "P$1") (pinfunction "P$1_P$1") (pintype "bidirectional"))
      (node (ref "U$18") (pin "P$1") (pinfunction "P$1_P$1") (pintype "bidirectional"))
      (node (ref "U$28") (pin "P$1") (pinfunction "P$1_P$1") (pintype "bidirectional"))
      (node (ref "U$6") (pin "P$1") (pinfunction "P$1_P$1") (pintype "bidirectional"))
      (node (ref "U1") (pin "P$12") (pinfunction "12_AGND_P$12") (pintype "bidirectional"))
      (node (ref "U1") (pin "P$19") (pinfunction "19_DGND_P$19") (pintype "bidirectional"))
      (node (ref "U1") (pin "P$2") (pinfunction "2_AGND_P$2") (pintype "bidirectional"))
      (node (ref "U1") (pin "P$32") (pinfunction "32_TEST_P$32") (pintype "bidirectional"))
      (node (ref "U1") (pin "P$47") (pinfunction "47_DGND_P$47") (pintype "bidirectional"))
      (node (ref "U3") (pin "1") (pinfunction "1_ADJ/GND_1") (pintype "input"))
      (node (ref "V") (pin "4") (pinfunction "KL_4") (pintype "passive"))
    )
    (net (code "8") (name "IAN") (class "Default")
      (node (ref "C16") (pin "P$1") (pinfunction "P$1_P$1") (pintype "bidirectional"))
      (node (ref "R46") (pin "P$2") (pinfunction "P$2_P$2") (pintype "bidirectional"))
      (node (ref "U1") (pin "P$4") (pinfunction "4_I1N_P$4") (pintype "bidirectional"))
    )
    (net (code "9") (name "IAP") (class "Default")
      (node (ref "C11") (pin "P$2") (pinfunction "P$2_P$2") (pintype "bidirectional"))
      (node (ref "R35") (pin "P$2") (pinfunction "P$2_P$2") (pintype "bidirectional"))
      (node (ref "U1") (pin "P$3") (pinfunction "3_I1P_P$3") (pintype "bidirectional"))
    )
    (net (code "10") (name "IBN") (class "Default")
      (node (ref "C20") (pin "P$1") (pinfunction "P$1_P$1") (pintype "bidirectional"))
      (node (ref "R55") (pin "P$2") (pinfunction "P$2_P$2") (pintype "bidirectional"))
      (node (ref "U1") (pin "P$6") (pinfunction "6_I2N_P$6") (pintype "bidirectional"))
    )
    (net (code "11") (name "IBP") (class "Default")
      (node (ref "C18") (pin "P$2") (pinfunction "P$2_P$2") (pintype "bidirectional"))
      (node (ref "R49") (pin "P$2") (pinfunction "P$2_P$2") (pintype "bidirectional"))
      (node (ref "U1") (pin "P$5") (pinfunction "5_I2P_P$5") (pintype "bidirectional"))
    )
    (net (code "12") (name "ICN") (class "Default")
      (node (ref "C17") (pin "P$1") (pinfunction "P$1_P$1") (pintype "bidirectional"))
      (node (ref "R47") (pin "P$2") (pinfunction "P$2_P$2") (pintype "bidirectional"))
      (node (ref "U1") (pin "P$8") (pinfunction "8_I3N_P$8") (pintype "bidirectional"))
    )
    (net (code "13") (name "ICP") (class "Default")
      (node (ref "C12") (pin "P$2") (pinfunction "P$2_P$2") (pintype "bidirectional"))
      (node (ref "R36") (pin "P$2") (pinfunction "P$2_P$2") (pintype "bidirectional"))
      (node (ref "U1") (pin "P$7") (pinfunction "7_I3P_P$7") (pintype "bidirectional"))
    )
    (net (code "14") (name "INN") (class "Default")
      (node (ref "C21") (pin "P$1") (pinfunction "P$1_P$1") (pintype "bidirectional"))
      (node (ref "R56") (pin "P$2") (pinfunction "P$2_P$2") (pintype "bidirectional"))
      (node (ref "U1") (pin "P$10") (pinfunction "10_I4N_P$10") (pintype "bidirectional"))
    )
    (net (code "15") (name "INP") (class "Default")
      (node (ref "C19") (pin "P$2") (pinfunction "P$2_P$2") (pintype "bidirectional"))
      (node (ref "R50") (pin "P$2") (pinfunction "P$2_P$2") (pintype "bidirectional"))
      (node (ref "U1") (pin "P$9") (pinfunction "9_I4P_P$9") (pintype "bidirectional"))
    )
    (net (code "16") (name "IRQ0") (class "Default")
      (node (ref "PM2") (pin "2") (pinfunction "2_2") (pintype "passive"))
      (node (ref "U$12") (pin "P$1") (pinfunction "P$1_P$1") (pintype "bidirectional"))
      (node (ref "U$20") (pin "P$1") (pinfunction "P$1_P$1") (pintype "bidirectional"))
      (node (ref "U1") (pin "P$30") (pinfunction "30_IRQ0_P$30") (pintype "bidirectional"))
    )
    (net (code "17") (name "IRQ1") (class "Default")
      (node (ref "PM2") (pin "1") (pinfunction "1_1") (pintype "passive"))
      (node (ref "U$11") (pin "P$1") (pinfunction "P$1_P$1") (pintype "bidirectional"))
      (node (ref "U$19") (pin "P$1") (pinfunction "P$1_P$1") (pintype "bidirectional"))
      (node (ref "U1") (pin "P$31") (pinfunction "31_IRQ1_P$31") (pintype "bidirectional"))
    )
    (net (code "18") (name "Net-(C22-PadP$2)") (class "Default")
      (node (ref "C22") (pin "P$2") (pinfunction "P$2_P$2") (pintype "bidirectional"))
      (node (ref "R35") (pin "P$1") (pinfunction "P$1_P$1") (pintype "bidirectional"))
      (node (ref "R38") (pin "P$1") (pinfunction "P$1_P$1") (pintype "bidirectional"))
    )
    (net (code "19") (name "Net-(C23-PadP$2)") (class "Default")
      (node (ref "C23") (pin "P$2") (pinfunction "P$2_P$2") (pintype "bidirectional"))
      (node (ref "R49") (pin "P$1") (pinfunction "P$1_P$1") (pintype "bidirectional"))
      (node (ref "R51") (pin "P$1") (pinfunction "P$1_P$1") (pintype "bidirectional"))
    )
    (net (code "20") (name "Net-(C24-PadP$1)") (class "Default")
      (node (ref "C24") (pin "P$1") (pinfunction "P$1_P$1") (pintype "bidirectional"))
      (node (ref "R44") (pin "P$2") (pinfunction "P$2_P$2") (pintype "bidirectional"))
      (node (ref "R46") (pin "P$1") (pinfunction "P$1_P$1") (pintype "bidirectional"))
    )
    (net (code "21") (name "Net-(C25-PadP$1)") (class "Default")
      (node (ref "C25") (pin "P$1") (pinfunction "P$1_P$1") (pintype "bidirectional"))
      (node (ref "R53") (pin "P$1") (pinfunction "P$1_P$1") (pintype "bidirectional"))
      (node (ref "R55") (pin "P$1") (pinfunction "P$1_P$1") (pintype "bidirectional"))
    )
    (net (code "22") (name "Net-(C26-PadP$2)") (class "Default")
      (node (ref "C26") (pin "P$2") (pinfunction "P$2_P$2") (pintype "bidirectional"))
      (node (ref "R36") (pin "P$1") (pinfunction "P$1_P$1") (pintype "bidirectional"))
      (node (ref "R39") (pin "P$2") (pinfunction "P$2_P$2") (pintype "bidirectional"))
    )
    (net (code "23") (name "Net-(C27-PadP$2)") (class "Default")
      (node (ref "C27") (pin "P$2") (pinfunction "P$2_P$2") (pintype "bidirectional"))
      (node (ref "R50") (pin "P$1") (pinfunction "P$1_P$1") (pintype "bidirectional"))
      (node (ref "R52") (pin "P$1") (pinfunction "P$1_P$1") (pintype "bidirectional"))
    )
    (net (code "24") (name "Net-(C28-PadP$1)") (class "Default")
      (node (ref "C28") (pin "P$1") (pinfunction "P$1_P$1") (pintype "bidirectional"))
      (node (ref "R45") (pin "P$1") (pinfunction "P$1_P$1") (pintype "bidirectional"))
      (node (ref "R47") (pin "P$1") (pinfunction "P$1_P$1") (pintype "bidirectional"))
    )
    (net (code "25") (name "Net-(C29-PadP$1)") (class "Default")
      (node (ref "C29") (pin "P$1") (pinfunction "P$1_P$1") (pintype "bidirectional"))
      (node (ref "R54") (pin "P$1") (pinfunction "P$1_P$1") (pintype "bidirectional"))
      (node (ref "R56") (pin "P$1") (pinfunction "P$1_P$1") (pintype "bidirectional"))
    )
    (net (code "26") (name "Net-(IAA-KL)") (class "Default")
      (node (ref "IA") (pin "1") (pinfunction "KL_1") (pintype "passive"))
      (node (ref "R38") (pin "P$2") (pinfunction "P$2_P$2") (pintype "bidirectional"))
    )
    (net (code "27") (name "Net-(IAB-KL)") (class "Default")
      (node (ref "IA") (pin "2") (pinfunction "KL_2") (pintype "passive"))
      (node (ref "R44") (pin "P$1") (pinfunction "P$1_P$1") (pintype "bidirectional"))
    )
    (net (code "28") (name "Net-(IBA-KL)") (class "Default")
      (node (ref "IB") (pin "1") (pinfunction "KL_1") (pintype "passive"))
      (node (ref "R51") (pin "P$2") (pinfunction "P$2_P$2") (pintype "bidirectional"))
    )
    (net (code "29") (name "Net-(IBB-KL)") (class "Default")
      (node (ref "IB") (pin "2") (pinfunction "KL_2") (pintype "passive"))
      (node (ref "R53") (pin "P$2") (pinfunction "P$2_P$2") (pintype "bidirectional"))
    )
    (net (code "30") (name "Net-(ICA-KL)") (class "Default")
      (node (ref "IC") (pin "1") (pinfunction "KL_1") (pintype "passive"))
      (node (ref "R39") (pin "P$1") (pinfunction "P$1_P$1") (pintype "bidirectional"))
    )
    (net (code "31") (name "Net-(ICB-KL)") (class "Default")
      (node (ref "IC") (pin "2") (pinfunction "KL_2") (pintype "passive"))
      (node (ref "R45") (pin "P$2") (pinfunction "P$2_P$2") (pintype "bidirectional"))
    )
    (net (code "32") (name "Net-(INA-KL)") (class "Default")
      (node (ref "IN") (pin "1") (pinfunction "KL_1") (pintype "passive"))
      (node (ref "R52") (pin "P$2") (pinfunction "P$2_P$2") (pintype "bidirectional"))
    )
    (net (code "33") (name "Net-(INB-KL)") (class "Default")
      (node (ref "IN") (pin "2") (pinfunction "KL_2") (pintype "passive"))
      (node (ref "R54") (pin "P$2") (pinfunction "P$2_P$2") (pintype "bidirectional"))
    )
    (net (code "34") (name "Net-(LED1-PadC)") (class "Default")
      (node (ref "LED1") (pin "C") (pinfunction "C_C") (pintype "passive"))
      (node (ref "R34") (pin "P$1") (pinfunction "P$1_P$1") (pintype "bidirectional"))
    )
    (net (code "35") (name "Net-(LED2-PadC)") (class "Default")
      (node (ref "LED2") (pin "C") (pinfunction "C_C") (pintype "passive"))
      (node (ref "R37") (pin "P$1") (pinfunction "P$1_P$1") (pintype "bidirectional"))
    )
    (net (code "36") (name "Net-(LED3-PadC)") (class "Default")
      (node (ref "LED3") (pin "C") (pinfunction "C_C") (pintype "passive"))
      (node (ref "R42") (pin "P$1") (pinfunction "P$1_P$1") (pintype "bidirectional"))
    )
    (net (code "37") (name "Net-(LED4-PadC)") (class "Default")
      (node (ref "LED4") (pin "C") (pinfunction "C_C") (pintype "passive"))
      (node (ref "R48") (pin "P$1") (pinfunction "P$1_P$1") (pintype "bidirectional"))
    )
    (net (code "38") (name "Net-(PULLUP-Pad1)") (class "Default")
      (node (ref "PULLUP") (pin "1") (pinfunction "1_1") (pintype "passive"))
      (node (ref "R11") (pin "P$2") (pinfunction "P$2_P$2") (pintype "bidirectional"))
      (node (ref "R12") (pin "P$2") (pinfunction "P$2_P$2") (pintype "bidirectional"))
      (node (ref "R13") (pin "P$2") (pinfunction "P$2_P$2") (pintype "bidirectional"))
      (node (ref "R14") (pin "P$2") (pinfunction "P$2_P$2") (pintype "bidirectional"))
    )
    (net (code "39") (name "Net-(R3-PadP$2)") (class "Default")
      (node (ref "R3") (pin "P$2") (pinfunction "P$2_P$2") (pintype "bidirectional"))
      (node (ref "R4") (pin "P$1") (pinfunction "P$1_P$1") (pintype "bidirectional"))
    )
    (net (code "40") (name "Net-(R4-PadP$2)") (class "Default")
      (node (ref "R4") (pin "P$2") (pinfunction "P$2_P$2") (pintype "bidirectional"))
      (node (ref "R5") (pin "P$1") (pinfunction "P$1_P$1") (pintype "bidirectional"))
    )
    (net (code "41") (name "Net-(R5-PadP$2)") (class "Default")
      (node (ref "R5") (pin "P$2") (pinfunction "P$2_P$2") (pintype "bidirectional"))
      (node (ref "R6") (pin "P$1") (pinfunction "P$1_P$1") (pintype "bidirectional"))
    )
    (net (code "42") (name "Net-(R6-PadP$2)") (class "Default")
      (node (ref "R6") (pin "P$2") (pinfunction "P$2_P$2") (pintype "bidirectional"))
      (node (ref "R7") (pin "P$1") (pinfunction "P$1_P$1") (pintype "bidirectional"))
    )
    (net (code "43") (name "Net-(R7-PadP$2)") (class "Default")
      (node (ref "R7") (pin "P$2") (pinfunction "P$2_P$2") (pintype "bidirectional"))
      (node (ref "R8") (pin "P$1") (pinfunction "P$1_P$1") (pintype "bidirectional"))
    )
    (net (code "44") (name "Net-(R8-PadP$2)") (class "Default")
      (node (ref "R8") (pin "P$2") (pinfunction "P$2_P$2") (pintype "bidirectional"))
      (node (ref "R9") (pin "P$1") (pinfunction "P$1_P$1") (pintype "bidirectional"))
    )
    (net (code "45") (name "Net-(R16-PadP$2)") (class "Default")
      (node (ref "R16") (pin "P$2") (pinfunction "P$2_P$2") (pintype "bidirectional"))
      (node (ref "R17") (pin "P$1") (pinfunction "P$1_P$1") (pintype "bidirectional"))
    )
    (net (code "46") (name "Net-(R17-PadP$2)") (class "Default")
      (node (ref "R17") (pin "P$2") (pinfunction "P$2_P$2") (pintype "bidirectional"))
      (node (ref "R18") (pin "P$1") (pinfunction "P$1_P$1") (pintype "bidirectional"))
    )
    (net (code "47") (name "Net-(R18-PadP$2)") (class "Default")
      (node (ref "R18") (pin "P$2") (pinfunction "P$2_P$2") (pintype "bidirectional"))
      (node (ref "R19") (pin "P$1") (pinfunction "P$1_P$1") (pintype "bidirectional"))
    )
    (net (code "48") (name "Net-(R19-PadP$2)") (class "Default")
      (node (ref "R19") (pin "P$2") (pinfunction "P$2_P$2") (pintype "bidirectional"))
      (node (ref "R20") (pin "P$1") (pinfunction "P$1_P$1") (pintype "bidirectional"))
    )
    (net (code "49") (name "Net-(R20-PadP$2)") (class "Default")
      (node (ref "R20") (pin "P$2") (pinfunction "P$2_P$2") (pintype "bidirectional"))
      (node (ref "R21") (pin "P$1") (pinfunction "P$1_P$1") (pintype "bidirectional"))
    )
    (net (code "50") (name "Net-(R21-PadP$2)") (class "Default")
      (node (ref "R21") (pin "P$2") (pinfunction "P$2_P$2") (pintype "bidirectional"))
      (node (ref "R22") (pin "P$1") (pinfunction "P$1_P$1") (pintype "bidirectional"))
    )
    (net (code "51") (name "Net-(R25-PadP$2)") (class "Default")
      (node (ref "R25") (pin "P$2") (pinfunction "P$2_P$2") (pintype "bidirectional"))
      (node (ref "R26") (pin "P$1") (pinfunction "P$1_P$1") (pintype "bidirectional"))
    )
    (net (code "52") (name "Net-(R26-PadP$2)") (class "Default")
      (node (ref "R26") (pin "P$2") (pinfunction "P$2_P$2") (pintype "bidirectional"))
      (node (ref "R27") (pin "P$1") (pinfunction "P$1_P$1") (pintype "bidirectional"))
    )
    (net (code "53") (name "Net-(R27-PadP$2)") (class "Default")
      (node (ref "R27") (pin "P$2") (pinfunction "P$2_P$2") (pintype "bidirectional"))
      (node (ref "R28") (pin "P$1") (pinfunction "P$1_P$1") (pintype "bidirectional"))
    )
    (net (code "54") (name "Net-(R28-PadP$2)") (class "Default")
      (node (ref "R28") (pin "P$2") (pinfunction "P$2_P$2") (pintype "bidirectional"))
      (node (ref "R29") (pin "P$1") (pinfunction "P$1_P$1") (pintype "bidirectional"))
    )
    (net (code "55") (name "Net-(R29-PadP$2)") (class "Default")
      (node (ref "R29") (pin "P$2") (pinfunction "P$2_P$2") (pintype "bidirectional"))
      (node (ref "R30") (pin "P$1") (pinfunction "P$1_P$1") (pintype "bidirectional"))
    )
    (net (code "56") (name "Net-(R30-PadP$2)") (class "Default")
      (node (ref "R30") (pin "P$2") (pinfunction "P$2_P$2") (pintype "bidirectional"))
      (node (ref "R31") (pin "P$1") (pinfunction "P$1_P$1") (pintype "bidirectional"))
    )
    (net (code "57") (name "Net-(U1-20_OSCI)") (class "Default")
      (node (ref "Q1") (pin "2") (pinfunction "2_2") (pintype "passive"))
      (node (ref "U1") (pin "P$20") (pinfunction "20_OSCI_P$20") (pintype "bidirectional"))
    )
    (net (code "58") (name "Net-(U1-21_OSCO)") (class "Default")
      (node (ref "Q1") (pin "1") (pinfunction "1_1") (pintype "passive"))
      (node (ref "U1") (pin "P$21") (pinfunction "21_OSCO_P$21") (pintype "bidirectional"))
    )
    (net (code "59") (name "Net-(U1-36_DMA_CRTL)") (class "Default")
      (node (ref "SJ1") (pin "2") (pinfunction "2_2") (pintype "passive"))
      (node (ref "U1") (pin "P$36") (pinfunction "36_DMA_CRTL_P$36") (pintype "bidirectional"))
    )
    (net (code "60") (name "Net-(VA-KL)") (class "Default")
      (node (ref "R3") (pin "P$1") (pinfunction "P$1_P$1") (pintype "bidirectional"))
      (node (ref "V") (pin "1") (pinfunction "KL_1") (pintype "passive"))
    )
    (net (code "61") (name "Net-(VB-KL)") (class "Default")
      (node (ref "R16") (pin "P$1") (pinfunction "P$1_P$1") (pintype "bidirectional"))
      (node (ref "V") (pin "2") (pinfunction "KL_2") (pintype "passive"))
    )
    (net (code "62") (name "Net-(VC-KL)") (class "Default")
      (node (ref "R25") (pin "P$1") (pinfunction "P$1_P$1") (pintype "bidirectional"))
      (node (ref "V") (pin "3") (pinfunction "KL_3") (pintype "passive"))
    )
    (net (code "63") (name "PM0") (class "Default")
      (node (ref "PM0") (pin "2") (pinfunction "2_2") (pintype "passive"))
      (node (ref "U1") (pin "P$33") (pinfunction "33_PM0_P$33") (pintype "bidirectional"))
    )
    (net (code "64") (name "PM1") (class "Default")
      (node (ref "PM1") (pin "2") (pinfunction "2_2") (pintype "passive"))
      (node (ref "U1") (pin "P$34") (pinfunction "34_PM1_P$34") (pintype "bidirectional"))
    )
    (net (code "65") (name "RESET_M90") (class "Default")
      (node (ref "C1") (pin "P$2") (pinfunction "P$2_P$2") (pintype "bidirectional"))
      (node (ref "JP1") (pin "2") (pinfunction "2_2") (pintype "passive"))
      (node (ref "R2") (pin "P$1") (pinfunction "P$1_P$1") (pintype "bidirectional"))
      (node (ref "RESET") (pin "P$3") (pinfunction "3_P$3") (pintype "bidirectional"))
      (node (ref "RESET") (pin "P$4") (pinfunction "4_P$4") (pintype "bidirectional"))
      (node (ref "U$14") (pin "P$1") (pinfunction "P$1_P$1") (pintype "bidirectional"))
      (node (ref "U$27") (pin "P$1") (pinfunction "P$1_P$1") (pintype "bidirectional"))
      (node (ref "U1") (pin "P$41") (pinfunction "41_~{RESET}_P$41") (pintype "bidirectional"))
    )
    (net (code "66") (name "SCLK") (class "Default")
      (node (ref "JP1") (pin "5") (pinfunction "5_5") (pintype "passive"))
      (node (ref "R13") (pin "P$1") (pinfunction "P$1_P$1") (pintype "bidirectional"))
      (node (ref "U$24") (pin "P$1") (pinfunction "P$1_P$1") (pintype "bidirectional"))
      (node (ref "U$3") (pin "P$1") (pinfunction "P$1_P$1") (pintype "bidirectional"))
      (node (ref "U1") (pin "P$38") (pinfunction "38_SCLK_P$38") (pintype "bidirectional"))
    )
    (net (code "67") (name "SDI") (class "Default")
      (node (ref "JP1") (pin "3") (pinfunction "3_3") (pintype "passive"))
      (node (ref "R11") (pin "P$1") (pinfunction "P$1_P$1") (pintype "bidirectional"))
      (node (ref "U$1") (pin "P$1") (pinfunction "P$1_P$1") (pintype "bidirectional"))
      (node (ref "U$22") (pin "P$1") (pinfunction "P$1_P$1") (pintype "bidirectional"))
      (node (ref "U1") (pin "P$40") (pinfunction "40_SDI_P$40") (pintype "bidirectional"))
    )
    (net (code "68") (name "SDO") (class "Default")
      (node (ref "JP1") (pin "4") (pinfunction "4_4") (pintype "passive"))
      (node (ref "R12") (pin "P$1") (pinfunction "P$1_P$1") (pintype "bidirectional"))
      (node (ref "U$2") (pin "P$1") (pinfunction "P$1_P$1") (pintype "bidirectional"))
      (node (ref "U$23") (pin "P$1") (pinfunction "P$1_P$1") (pintype "bidirectional"))
      (node (ref "U1") (pin "P$39") (pinfunction "39_SDO_P$39") (pintype "bidirectional"))
    )
    (net (code "69") (name "V1N") (class "Default")
      (node (ref "C13") (pin "P$2") (pinfunction "P$2_P$2") (pintype "bidirectional"))
      (node (ref "R40") (pin "P$2") (pinfunction "P$2_P$2") (pintype "bidirectional"))
      (node (ref "U1") (pin "P$14") (pinfunction "14_V1N_P$14") (pintype "bidirectional"))
    )
    (net (code "70") (name "V2N") (class "Default")
      (node (ref "C14") (pin "P$2") (pinfunction "P$2_P$2") (pintype "bidirectional"))
      (node (ref "R41") (pin "P$2") (pinfunction "P$2_P$2") (pintype "bidirectional"))
      (node (ref "U1") (pin "P$16") (pinfunction "16_V2N_P$16") (pintype "bidirectional"))
    )
    (net (code "71") (name "V3N") (class "Default")
      (node (ref "C15") (pin "P$2") (pinfunction "P$2_P$2") (pintype "bidirectional"))
      (node (ref "R43") (pin "P$2") (pinfunction "P$2_P$2") (pintype "bidirectional"))
      (node (ref "U1") (pin "P$18") (pinfunction "18_V3N_P$18") (pintype "bidirectional"))
    )
    (net (code "72") (name "VAP") (class "Default")
      (node (ref "C3") (pin "P$2") (pinfunction "P$2_P$2") (pintype "bidirectional"))
      (node (ref "R10") (pin "P$2") (pinfunction "P$2_P$2") (pintype "bidirectional"))
      (node (ref "R9") (pin "P$2") (pinfunction "P$2_P$2") (pintype "bidirectional"))
      (node (ref "U1") (pin "P$13") (pinfunction "13_V1P_P$13") (pintype "bidirectional"))
    )
    (net (code "73") (name "VBP") (class "Default")
      (node (ref "C6") (pin "P$2") (pinfunction "P$2_P$2") (pintype "bidirectional"))
      (node (ref "R22") (pin "P$2") (pinfunction "P$2_P$2") (pintype "bidirectional"))
      (node (ref "R23") (pin "P$2") (pinfunction "P$2_P$2") (pintype "bidirectional"))
      (node (ref "U1") (pin "P$15") (pinfunction "15_V2P_P$15") (pintype "bidirectional"))
    )
    (net (code "74") (name "VCP") (class "Default")
      (node (ref "C8") (pin "P$2") (pinfunction "P$2_P$2") (pintype "bidirectional"))
      (node (ref "R31") (pin "P$2") (pinfunction "P$2_P$2") (pintype "bidirectional"))
      (node (ref "R32") (pin "P$2") (pinfunction "P$2_P$2") (pintype "bidirectional"))
      (node (ref "U1") (pin "P$17") (pinfunction "17_V3P_P$17") (pintype "bidirectional"))
    )
    (net (code "75") (name "VDD") (class "Default")
      (node (ref "3V3_ISO") (pin "TP") (pinfunction "TP_TP") (pintype "input"))
      (node (ref "C32") (pin "P$2") (pinfunction "P$2_P$2") (pintype "bidirectional"))
      (node (ref "C5") (pin "P$2") (pinfunction "P$2_P$2") (pintype "bidirectional"))
      (node (ref "C7") (pin "P$2") (pinfunction "P$2_P$2") (pintype "bidirectional"))
      (node (ref "JP1") (pin "1") (pinfunction "1_1") (pintype "passive"))
      (node (ref "PM0") (pin "1") (pinfunction "1_1") (pintype "passive"))
      (node (ref "PM1") (pin "1") (pinfunction "1_1") (pintype "passive"))
      (node (ref "PULLUP") (pin "2") (pinfunction "2_2") (pintype "passive"))
      (node (ref "PWR") (pin "2") (pinfunction "KL_2") (pintype "passive"))
      (node (ref "R2") (pin "P$2") (pinfunction "P$2_P$2") (pintype "bidirectional"))
      (node (ref "SJ1") (pin "1") (pinfunction "1_1") (pintype "passive"))
      (node (ref "U$26") (pin "P$1") (pinfunction "P$1_P$1") (pintype "bidirectional"))
      (node (ref "U$5") (pin "P$1") (pinfunction "P$1_P$1") (pintype "bidirectional"))
      (node (ref "U1") (pin "P$1") (pinfunction "1_AVDD_P$1") (pintype "bidirectional"))
      (node (ref "U1") (pin "P$48") (pinfunction "48_DVDD_P$48") (pintype "bidirectional"))
      (node (ref "U3") (pin "2") (pinfunction "2_OUT_2") (pintype "output"))
    )
    (net (code "76") (name "VDD18") (class "Default")
      (node (ref "1V8") (pin "TP") (pinfunction "TP_TP") (pintype "input"))
      (node (ref "C2") (pin "P$2") (pinfunction "P$2_P$2") (pintype "bidirectional"))
      (node (ref "C4") (pin "P$2") (pinfunction "P$2_P$2") (pintype "bidirectional"))
      (node (ref "U1") (pin "P$42") (pinfunction "42_VDD18_P$42") (pintype "bidirectional"))
      (node (ref "U1") (pin "P$43") (pinfunction "43_VDD18_P$43") (pintype "bidirectional"))
    )
    (net (code "77") (name "VREF") (class "Default")
      (node (ref "C10") (pin "P$2") (pinfunction "P$2_P$2") (pintype "bidirectional"))
      (node (ref "C9") (pin "P$2") (pinfunction "P$2_P$2") (pintype "bidirectional"))
      (node (ref "U1") (pin "P$11") (pinfunction "11_VREF_P$11") (pintype "bidirectional"))
    )
    (net (code "78") (name "WARN_OUT") (class "Default")
      (node (ref "PM2") (pin "3") (pinfunction "3_3") (pintype "passive"))
      (node (ref "U$13") (pin "P$1") (pinfunction "P$1_P$1") (pintype "bidirectional"))
      (node (ref "U$21") (pin "P$1") (pinfunction "P$1_P$1") (pintype "bidirectional"))
      (node (ref "U1") (pin "P$29") (pinfunction "29_WARN_OUT_P$29") (pintype "bidirectional"))
    )
    (net (code "79") (name "ZX0") (class "Default")
      (node (ref "JP4") (pin "3") (pinfunction "3_3") (pintype "passive"))
      (node (ref "U$17") (pin "P$1") (pinfunction "P$1_P$1") (pintype "bidirectional"))
      (node (ref "U$9") (pin "P$1") (pinfunction "P$1_P$1") (pintype "bidirectional"))
      (node (ref "U1") (pin "P$22") (pinfunction "22_ZX0_P$22") (pintype "bidirectional"))
    )
    (net (code "80") (name "ZX1") (class "Default")
      (node (ref "JP4") (pin "2") (pinfunction "2_2") (pintype "passive"))
      (node (ref "U$16") (pin "P$1") (pinfunction "P$1_P$1") (pintype "bidirectional"))
      (node (ref "U$8") (pin "P$1") (pinfunction "P$1_P$1") (pintype "bidirectional"))
      (node (ref "U1") (pin "P$23") (pinfunction "23_ZX1_P$23") (pintype "bidirectional"))
    )
    (net (code "81") (name "ZX2") (class "Default")
      (node (ref "JP4") (pin "1") (pinfunction "1_1") (pintype "passive"))
      (node (ref "U$15") (pin "P$1") (pinfunction "P$1_P$1") (pintype "bidirectional"))
      (node (ref "U$7") (pin "P$1") (pinfunction "P$1_P$1") (pintype "bidirectional"))
      (node (ref "U1") (pin "P$24") (pinfunction "24_ZX2_P$24") (pintype "bidirectional"))
    )
    (net (code "82") (name "unconnected-(U1-35_N.C.-PadP$35)") (class "Default")
      (node (ref "U1") (pin "P$35") (pinfunction "35_N.C._P$35") (pintype "bidirectional"))
    )
    (net (code "83") (name "unconnected-(U1-44_DGND-PadP$44)") (class "Default")
      (node (ref "U1") (pin "P$44") (pinfunction "44_DGND_P$44") (pintype "bidirectional"))
    )
    (net (code "84") (name "unconnected-(U1-45_N.C.-PadP$45)") (class "Default")
      (node (ref "U1") (pin "P$45") (pinfunction "45_N.C._P$45") (pintype "bidirectional"))
    )
    (net (code "85") (name "unconnected-(U1-46_N.C.-PadP$46)") (class "Default")
      (node (ref "U1") (pin "P$46") (pinfunction "46_N.C._P$46") (pintype "bidirectional"))
    )
  )
)
